# 687253_019_3_1.net
KiCad netlist of a schematic drawn in Altium Designer
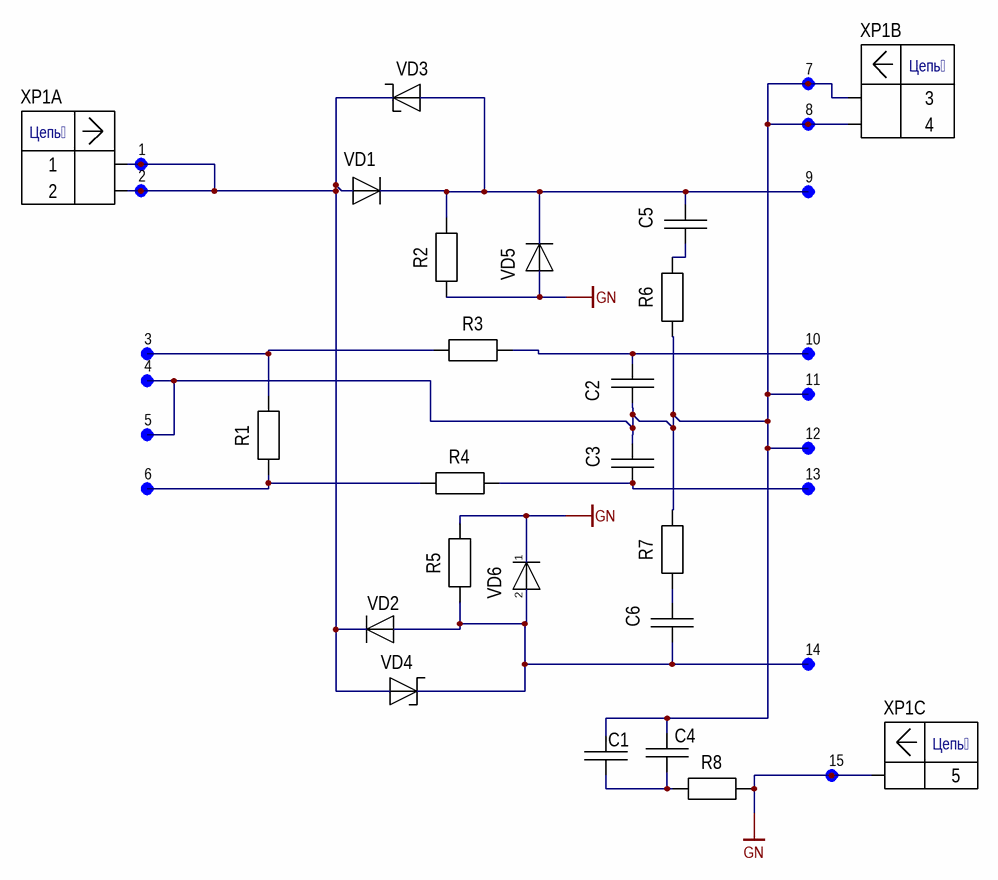
[diagram p0: УШЯИ.687253.019Э3_1.SchDoc]

(export (version "E")
  (design (tool "Eeschema 10.0.6"))
  (components
    (comp (ref "1") (value "OTV18") (footprint "OTV18") (libsource (lib "МНИПИ_Остальное") (part "OTV18")))
    (comp (ref "2") (value "OTV18") (footprint "OTV18") (libsource (lib "МНИПИ_Остальное") (part "OTV18")))
    (comp (ref "3") (value "OTV18") (footprint "OTV18") (libsource (lib "МНИПИ_Остальное") (part "OTV18")))
    (comp (ref "4") (value "OTV18") (footprint "OTV18") (libsource (lib "МНИПИ_Остальное") (part "OTV18")))
    (comp (ref "5") (value "OTV18") (footprint "OTV18") (libsource (lib "МНИПИ_Остальное") (part "OTV18")))
    (comp (ref "6") (value "OTV18") (footprint "OTV18") (libsource (lib "МНИПИ_Остальное") (part "OTV18")))
    (comp (ref "7") (value "OTV18") (footprint "OTV18") (libsource (lib "МНИПИ_Остальное") (part "OTV18")))
    (comp (ref "8") (value "OTV18") (footprint "OTV18") (libsource (lib "МНИПИ_Остальное") (part "OTV18")))
    (comp (ref "9") (value "OTV18") (footprint "OTV18") (libsource (lib "МНИПИ_Остальное") (part "OTV18")))
    (comp (ref "10") (value "OTV18") (footprint "OTV18") (libsource (lib "МНИПИ_Остальное") (part "OTV18")))
    (comp (ref "11") (value "OTV18") (footprint "OTV18") (libsource (lib "МНИПИ_Остальное") (part "OTV18")))
    (comp (ref "12") (value "OTV18") (footprint "OTV18") (libsource (lib "МНИПИ_Остальное") (part "OTV18")))
    (comp (ref "13") (value "OTV18") (footprint "OTV18") (libsource (lib "МНИПИ_Остальное") (part "OTV18")))
    (comp (ref "14") (value "OTV18") (footprint "OTV18") (libsource (lib "МНИПИ_Остальное") (part "OTV18")))
    (comp (ref "15") (value "OTV18") (footprint "OTV18") (libsource (lib "МНИПИ_Остальное") (part "OTV18")))
    (comp (ref "C1")
      (value "К73-17-250 В-1 мкФ +-20%")
      (footprint "К73-17-А20")
      (libsource (lib "МНИПИ_Конденсаторы") (part "К73-17-250 В-1 мкФ +-20%"))
    )
    (comp (ref "C2")
      (value "GRM2165C2A102JA01D")
      (footprint "GRM216 IPC_B")
      (description "0805 1000 pF 100 V ±5% Tolerance X7R Multilayer Ceramic Chip Capacitor")
      (fields (field (name "TOLERANCE") "5%"))
      (libsource (lib "МНИПИ_Конденсаторы") (part "GRM2165C2A102JA01D"))
    )
    (comp (ref "C3")
      (value "GRM2165C2A102JA01D")
      (footprint "GRM216 IPC_B")
      (description "0805 1000 pF 100 V ±5% Tolerance X7R Multilayer Ceramic Chip Capacitor")
      (fields (field (name "TOLERANCE") "5%"))
      (libsource (lib "МНИПИ_Конденсаторы") (part "GRM2165C2A102JA01D"))
    )
    (comp (ref "C4")
      (value "К73-17-250 В-1 мкФ +-20%")
      (footprint "К73-17-А20")
      (libsource (lib "МНИПИ_Конденсаторы") (part "К73-17-250 В-1 мкФ +-20%"))
    )
    (comp (ref "C5")
      (value "К73-17-250 В-0,47 мкФ +-20%")
      (footprint "К73-17-А20")
      (libsource (lib "МНИПИ_Конденсаторы") (part "К73-17-250 В-0,47 мкФ +-20%"))
    )
    (comp (ref "C6")
      (value "К73-17-250 В-0,47 мкФ +-20%")
      (footprint "К73-17-А20")
      (libsource (lib "МНИПИ_Конденсаторы") (part "К73-17-250 В-0,47 мкФ +-20%"))
    )
    (comp (ref "R1")
      (value "1206-9,1 кОм+-5%")
      (footprint "МНИПИ_Резисторы:1206")
      (libsource (lib "МНИПИ_Резисторы") (part "1206-9,1 кОм+-5%"))
    )
    (comp (ref "R2")
      (value "1206-9,1 кОм+-5%")
      (footprint "МНИПИ_Резисторы:1206")
      (libsource (lib "МНИПИ_Резисторы") (part "1206-9,1 кОм+-5%"))
    )
    (comp (ref "R3")
      (value "1206-240 Ом+-5%")
      (footprint "МНИПИ_Резисторы:1206")
      (libsource (lib "МНИПИ_Резисторы") (part "1206-240 Ом+-5%"))
    )
    (comp (ref "R4")
      (value "1206-240 Ом+-5%")
      (footprint "МНИПИ_Резисторы:1206")
      (libsource (lib "МНИПИ_Резисторы") (part "1206-240 Ом+-5%"))
    )
    (comp (ref "R5")
      (value "1206-9,1 кОм+-5%")
      (footprint "МНИПИ_Резисторы:1206")
      (libsource (lib "МНИПИ_Резисторы") (part "1206-9,1 кОм+-5%"))
    )
    (comp (ref "R6")
      (value "1206-150 Ом+-5%")
      (footprint "МНИПИ_Резисторы:1206")
      (libsource (lib "МНИПИ_Резисторы") (part "1206-150 Ом+-5%"))
    )
    (comp (ref "R7")
      (value "1206-150 Ом+-5%")
      (footprint "МНИПИ_Резисторы:1206")
      (libsource (lib "МНИПИ_Резисторы") (part "1206-150 Ом+-5%"))
    )
    (comp (ref "R8")
      (value "1206-100 Ом+-5%")
      (footprint "МНИПИ_Резисторы:1206")
      (libsource (lib "МНИПИ_Резисторы") (part "1206-100 Ом+-5%"))
    )
    (comp (ref "VD1")
      (value "43CTQ100")
      (footprint "TO-220(F)")
      (description "High Performance Schottky Rectifier, 2 x 20 A")
      (libsource (lib "МНИПИ_Диоды") (part "43CTQ100"))
    )
    (comp (ref "VD2")
      (value "43CTQ100")
      (footprint "TO-220(F)")
      (description "High Performance Schottky Rectifier, 2 x 20 A")
      (libsource (lib "МНИПИ_Диоды") (part "43CTQ100"))
    )
    (comp (ref "VD3")
      (value "1,5KE68CA")
      (footprint "DO-201")
      (description "Супрессор 1,5KE68CA")
      (libsource (lib "МНИПИ_Диоды") (part "1,5KE56CA"))
    )
    (comp (ref "VD4")
      (value "1,5KE68CA")
      (footprint "DO-201")
      (description "Супрессор 1,5KE68CA")
      (libsource (lib "МНИПИ_Диоды") (part "1,5KE56CA"))
    )
    (comp (ref "VD5")
      (value "1N4007")
      (footprint "DO-35")
      (description "General Purpose Plastic Rectifier")
      (libsource (lib "МНИПИ_Диоды") (part "1N4007"))
    )
    (comp (ref "VD6")
      (value "1N4007")
      (footprint "DO-35")
      (description "General Purpose Plastic Rectifier")
      (libsource (lib "") (part "1N4007_1"))
    )
    (comp (ref "XP1")
      (value "MNL-350810-1")
      (footprint "350810-1")
      (libsource (lib "МНИПИ_Разъемы") (part "MNL-350810-1"))
    )
  )
  (nets
    (net (code "1") (name "GN") (class "Default")
      (node (ref "15") (pin "1") (pinfunction "1_1") (pintype "passive"))
      (node (ref "R2") (pin "1") (pinfunction "1_1") (pintype "passive"))
      (node (ref "R5") (pin "2") (pinfunction "2_2") (pintype "passive"))
      (node (ref "R8") (pin "2") (pinfunction "1_2") (pintype "passive"))
      (node (ref "VD5") (pin "2") (pintype "passive"))
      (node (ref "VD6") (pin "1") (pintype "passive"))
      (node (ref "XP1") (pin "5") (pinfunction "5_5") (pintype "passive"))
    )
    (net (code "2") (name "Net-(1-Pad1)") (class "Default")
      (node (ref "1") (pin "1") (pinfunction "1_1") (pintype "passive"))
      (node (ref "2") (pin "1") (pinfunction "1_1") (pintype "passive"))
      (node (ref "VD1") (pin "1") (pintype "passive"))
      (node (ref "VD2") (pin "2") (pintype "passive"))
      (node (ref "VD3") (pin "1") (pinfunction "1_1") (pintype "passive"))
      (node (ref "VD4") (pin "2") (pinfunction "2_2") (pintype "passive"))
      (node (ref "XP1") (pin "1") (pinfunction "1_1") (pintype "passive"))
      (node (ref "XP1") (pin "2") (pinfunction "2_2") (pintype "passive"))
    )
    (net (code "3") (name "Net-(3-Pad1)") (class "Default")
      (node (ref "3") (pin "1") (pinfunction "1_1") (pintype "passive"))
      (node (ref "R1") (pin "2") (pinfunction "2_2") (pintype "passive"))
      (node (ref "R3") (pin "1") (pinfunction "1_1") (pintype "passive"))
    )
    (net (code "4") (name "Net-(6-Pad1)") (class "Default")
      (node (ref "6") (pin "1") (pinfunction "1_1") (pintype "passive"))
      (node (ref "R1") (pin "1") (pinfunction "1_1") (pintype "passive"))
      (node (ref "R4") (pin "1") (pinfunction "1_1") (pintype "passive"))
    )
    (net (code "5") (name "Net-(9-Pad1)") (class "Default")
      (node (ref "9") (pin "1") (pinfunction "1_1") (pintype "passive"))
      (node (ref "C5") (pin "2") (pinfunction "2_2") (pintype "passive"))
      (node (ref "R2") (pin "2") (pinfunction "2_2") (pintype "passive"))
      (node (ref "VD1") (pin "2") (pintype "passive"))
      (node (ref "VD3") (pin "2") (pinfunction "2_2") (pintype "passive"))
      (node (ref "VD5") (pin "1") (pintype "passive"))
    )
    (net (code "6") (name "Net-(10-Pad1)") (class "Default")
      (node (ref "10") (pin "1") (pinfunction "1_1") (pintype "passive"))
      (node (ref "C2") (pin "1") (pinfunction "1_1") (pintype "passive"))
      (node (ref "R3") (pin "2") (pinfunction "1_2") (pintype "passive"))
    )
    (net (code "7") (name "Net-(11-Pad1)") (class "Default")
      (node (ref "11") (pin "1") (pinfunction "1_1") (pintype "passive"))
      (node (ref "12") (pin "1") (pinfunction "1_1") (pintype "passive"))
      (node (ref "4") (pin "1") (pinfunction "1_1") (pintype "passive"))
      (node (ref "5") (pin "1") (pinfunction "1_1") (pintype "passive"))
      (node (ref "7") (pin "1") (pinfunction "1_1") (pintype "passive"))
      (node (ref "8") (pin "1") (pinfunction "1_1") (pintype "passive"))
      (node (ref "C1") (pin "2") (pinfunction "2_2") (pintype "passive"))
      (node (ref "C2") (pin "2") (pinfunction "2_2") (pintype "passive"))
      (node (ref "C3") (pin "2") (pinfunction "2_2") (pintype "passive"))
      (node (ref "C4") (pin "2") (pinfunction "2_2") (pintype "passive"))
      (node (ref "R6") (pin "1") (pinfunction "1_1") (pintype "passive"))
      (node (ref "R7") (pin "2") (pinfunction "1_2") (pintype "passive"))
      (node (ref "XP1") (pin "3") (pinfunction "3_3") (pintype "passive"))
      (node (ref "XP1") (pin "4") (pinfunction "4_4") (pintype "passive"))
    )
    (net (code "8") (name "Net-(13-Pad1)") (class "Default")
      (node (ref "13") (pin "1") (pinfunction "1_1") (pintype "passive"))
      (node (ref "C3") (pin "1") (pinfunction "1_1") (pintype "passive"))
      (node (ref "R4") (pin "2") (pinfunction "1_2") (pintype "passive"))
    )
    (net (code "9") (name "Net-(14-Pad1)") (class "Default")
      (node (ref "14") (pin "1") (pinfunction "1_1") (pintype "passive"))
      (node (ref "C6") (pin "1") (pinfunction "1_1") (pintype "passive"))
      (node (ref "R5") (pin "1") (pinfunction "1_1") (pintype "passive"))
      (node (ref "VD2") (pin "1") (pintype "passive"))
      (node (ref "VD4") (pin "1") (pinfunction "1_1") (pintype "passive"))
      (node (ref "VD6") (pin "2") (pintype "passive"))
    )
    (net (code "10") (name "Net-(C1-Pad1)") (class "Default")
      (node (ref "C1") (pin "1") (pinfunction "1_1") (pintype "passive"))
      (node (ref "C4") (pin "1") (pinfunction "1_1") (pintype "passive"))
      (node (ref "R8") (pin "1") (pinfunction "1_1") (pintype "passive"))
    )
    (net (code "11") (name "Net-(C5-Pad1)") (class "Default")
      (node (ref "C5") (pin "1") (pinfunction "1_1") (pintype "passive"))
      (node (ref "R6") (pin "2") (pinfunction "1_2") (pintype "passive"))
    )
    (net (code "12") (name "Net-(C6-Pad2)") (class "Default")
      (node (ref "C6") (pin "2") (pinfunction "2_2") (pintype "passive"))
      (node (ref "R7") (pin "1") (pinfunction "1_1") (pintype "passive"))
    )
  )
)
